# SkiMeter.net
KiCad netlist of a schematic drawn in EAGLE
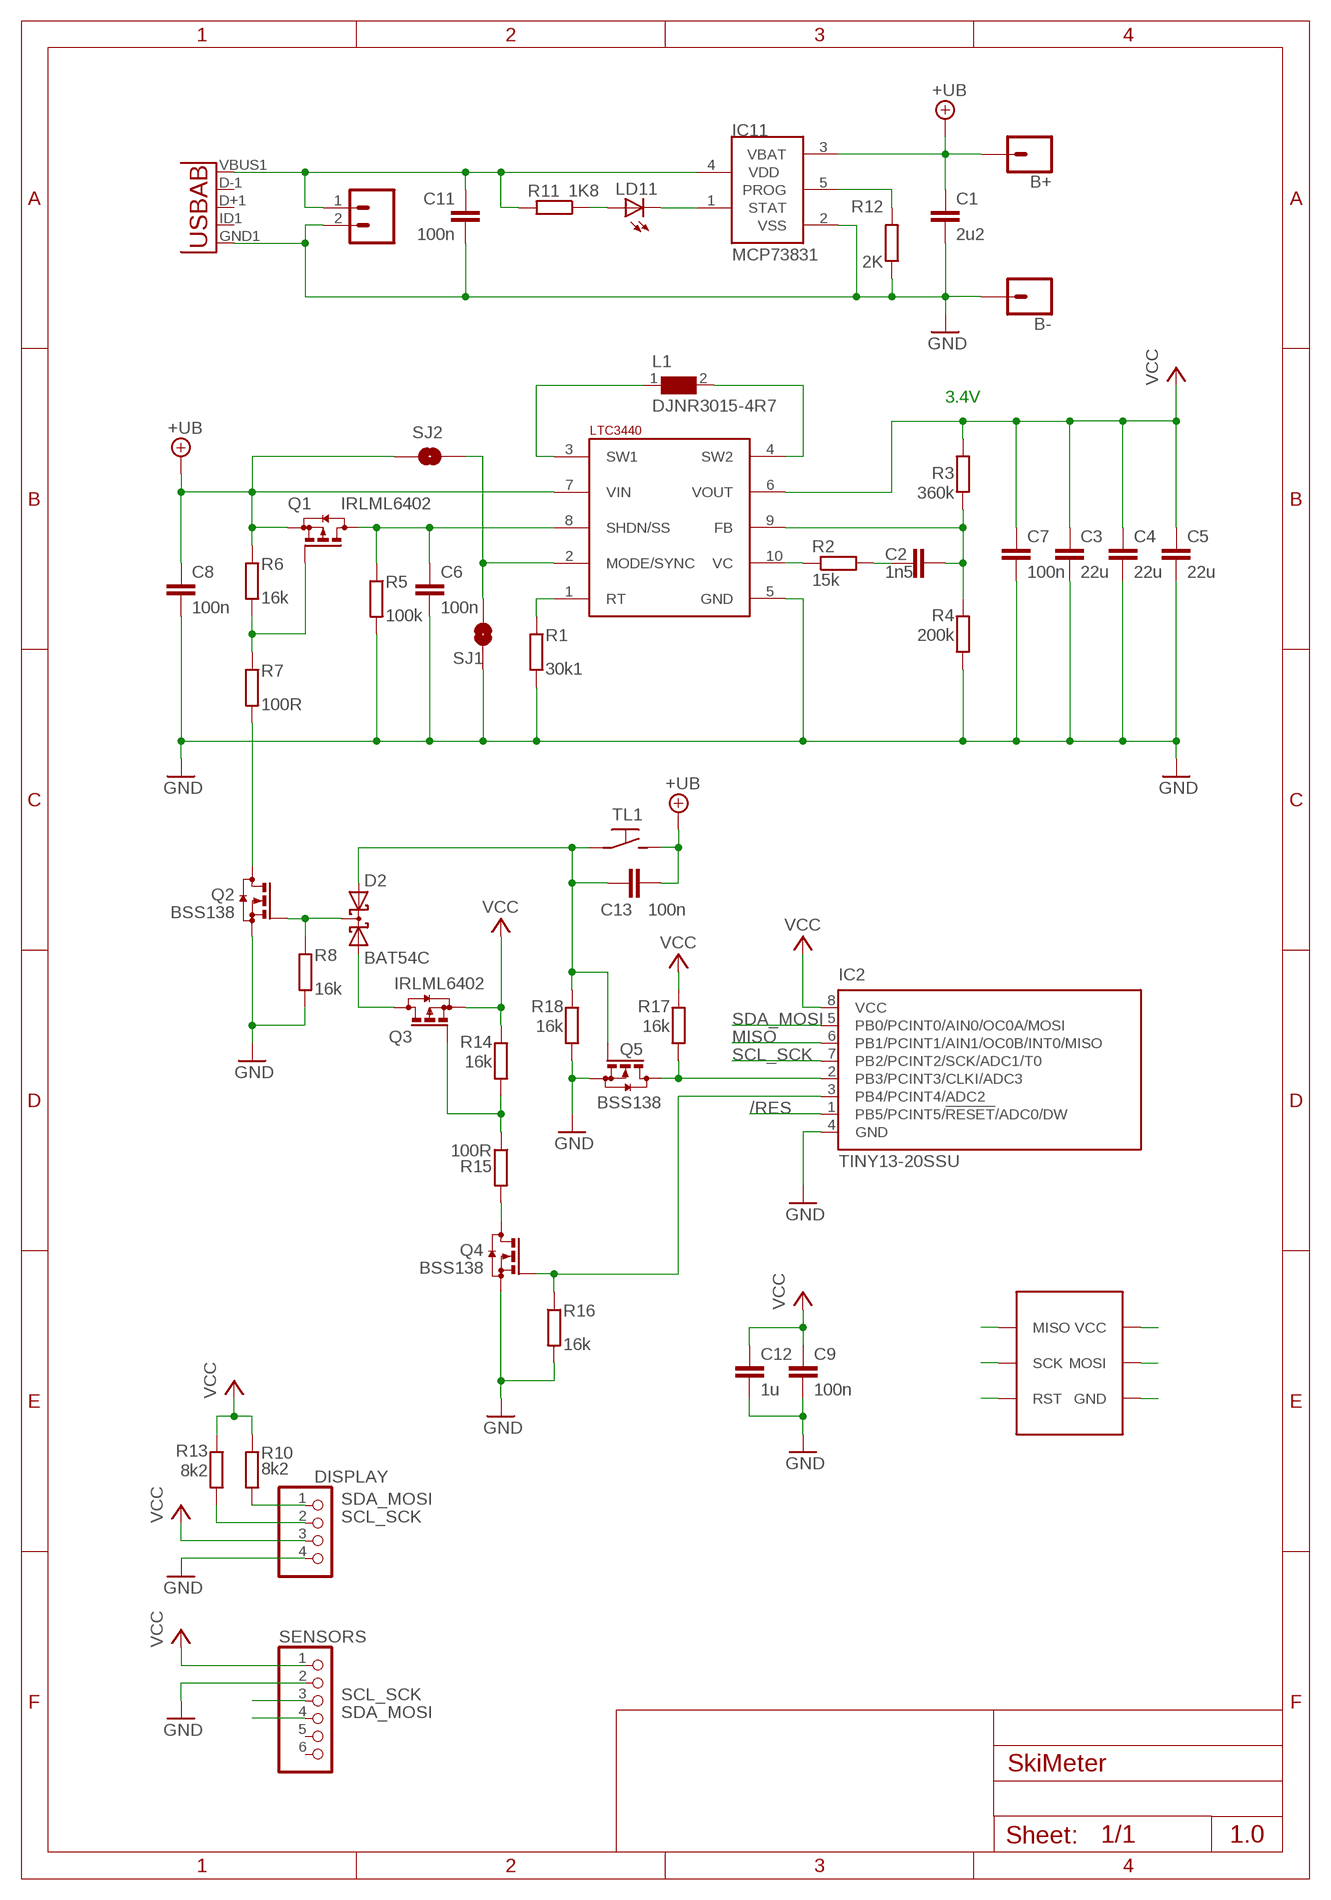
[diagram p0: schematic, sheet 1]

(export (version "E")
  (design (tool "Eeschema 10.0.6"))
  (components
    (comp (ref "+")
      (value "CONN_02")
      (footprint "eagle-import:1X02")
      (libsource (lib "eagle-import") (part "CONN_02"))
    )
    (comp (ref "B+")
      (value "CONN_01")
      (footprint "eagle-import:1X01")
      (libsource (lib "eagle-import") (part "CONN_01"))
    )
    (comp (ref "B-")
      (value "CONN_01")
      (footprint "eagle-import:1X01")
      (libsource (lib "eagle-import") (part "CONN_01"))
    )
    (comp (ref "C1")
      (value "2u2")
      (footprint "eagle-import:C0805")
      (libsource (lib "eagle-import") (part "C-EUC0805"))
    )
    (comp (ref "C2")
      (value "1n5")
      (footprint "eagle-import:C0805")
      (libsource (lib "eagle-import") (part "C-EUC0805"))
    )
    (comp (ref "C3")
      (value "22u")
      (footprint "eagle-import:C0805")
      (libsource (lib "eagle-import") (part "C-EUC0805"))
    )
    (comp (ref "C4")
      (value "22u")
      (footprint "eagle-import:C0805")
      (libsource (lib "eagle-import") (part "C-EUC0805"))
    )
    (comp (ref "C5")
      (value "22u")
      (footprint "eagle-import:C0805")
      (libsource (lib "eagle-import") (part "C-EUC0805"))
    )
    (comp (ref "C6")
      (value "100n")
      (footprint "eagle-import:C0805")
      (libsource (lib "eagle-import") (part "C-EUC0805"))
    )
    (comp (ref "C7")
      (value "100n")
      (footprint "eagle-import:C0805")
      (libsource (lib "eagle-import") (part "C-EUC0805"))
    )
    (comp (ref "C8")
      (value "100n")
      (footprint "eagle-import:C0805")
      (libsource (lib "eagle-import") (part "C-EUC0805"))
    )
    (comp (ref "C9")
      (value "100n")
      (footprint "eagle-import:C0805")
      (libsource (lib "eagle-import") (part "C-EUC0805"))
    )
    (comp (ref "C11")
      (value "100n")
      (footprint "eagle-import:C0805")
      (libsource (lib "eagle-import") (part "C-EUC0805"))
    )
    (comp (ref "C12")
      (value "1u")
      (footprint "eagle-import:C0805")
      (libsource (lib "eagle-import") (part "C-EUC0805"))
    )
    (comp (ref "C13")
      (value "100n")
      (footprint "eagle-import:C0805")
      (libsource (lib "eagle-import") (part "C-EUC0805"))
    )
    (comp (ref "D2")
      (value "BAT54C")
      (footprint "eagle-import:SOT23")
      (libsource (lib "eagle-import") (part "BAT54C"))
    )
    (comp (ref "DISPLAY")
      (value "PINHD-1X4")
      (footprint "eagle-import:1X04")
      (libsource (lib "eagle-import") (part "PINHD-1X4"))
    )
    (comp (ref "IC1")
      (value "LTC3440")
      (footprint "eagle-import:MSOP10")
      (libsource (lib "eagle-import") (part "LTC3440"))
    )
    (comp (ref "IC2")
      (value "TINY13-20SSU")
      (footprint "eagle-import:8S1")
      (fields (field (name "MPN") "ATTINY13-20SSU"))
      (libsource (lib "eagle-import") (part "TINY13SSU-20"))
    )
    (comp (ref "IC11")
      (value "MCP73831")
      (footprint "eagle-import:SOT23-5L")
      (libsource (lib "eagle-import") (part "MCP73831"))
    )
    (comp (ref "L1")
      (value "DJNR3015-4R7")
      (footprint "eagle-import:WE-LQS_3015")
      (libsource (lib "eagle-import") (part "WE-LQS_3015"))
    )
    (comp (ref "LD11")
      (value "LEDCHIPLED_0805")
      (footprint "eagle-import:CHIPLED_0805")
      (libsource (lib "eagle-import") (part "LEDCHIPLED_0805"))
    )
    (comp (ref "Q1")
      (value "IRLML6402")
      (footprint "eagle-import:SOT23")
      (libsource (lib "eagle-import") (part "BSS84"))
    )
    (comp (ref "Q2")
      (value "BSS138")
      (footprint "eagle-import:SOT23")
      (libsource (lib "eagle-import") (part "BSS123"))
    )
    (comp (ref "Q3")
      (value "IRLML6402")
      (footprint "eagle-import:SOT23")
      (libsource (lib "eagle-import") (part "BSS84"))
    )
    (comp (ref "Q4")
      (value "BSS138")
      (footprint "eagle-import:SOT23")
      (libsource (lib "eagle-import") (part "BSS123"))
    )
    (comp (ref "Q5")
      (value "BSS138")
      (footprint "eagle-import:SOT23")
      (libsource (lib "eagle-import") (part "BSS123"))
    )
    (comp (ref "R1")
      (value "30k1")
      (footprint "eagle-import:M0805")
      (libsource (lib "eagle-import") (part "R-EU_M0805"))
    )
    (comp (ref "R2")
      (value "15k")
      (footprint "eagle-import:M0805")
      (libsource (lib "eagle-import") (part "R-EU_M0805"))
    )
    (comp (ref "R3")
      (value "360k")
      (footprint "eagle-import:M0805")
      (libsource (lib "eagle-import") (part "R-EU_M0805"))
    )
    (comp (ref "R4")
      (value "200k")
      (footprint "eagle-import:M0805")
      (libsource (lib "eagle-import") (part "R-EU_M0805"))
    )
    (comp (ref "R5")
      (value "100k")
      (footprint "eagle-import:M0805")
      (libsource (lib "eagle-import") (part "R-EU_M0805"))
    )
    (comp (ref "R6")
      (value "16k")
      (footprint "eagle-import:M0805")
      (libsource (lib "eagle-import") (part "R-EU_M0805"))
    )
    (comp (ref "R7")
      (value "100R")
      (footprint "eagle-import:M0805")
      (libsource (lib "eagle-import") (part "R-EU_M0805"))
    )
    (comp (ref "R8")
      (value "16k")
      (footprint "eagle-import:M0805")
      (libsource (lib "eagle-import") (part "R-EU_M0805"))
    )
    (comp (ref "R10")
      (value "8k2")
      (footprint "eagle-import:M0805")
      (libsource (lib "eagle-import") (part "R-EU_M0805"))
    )
    (comp (ref "R11")
      (value "1K8")
      (footprint "eagle-import:M0805")
      (libsource (lib "eagle-import") (part "R-EU_M0805"))
    )
    (comp (ref "R12")
      (value "2K")
      (footprint "eagle-import:M0805")
      (libsource (lib "eagle-import") (part "R-EU_M0805"))
    )
    (comp (ref "R13")
      (value "8k2")
      (footprint "eagle-import:M0805")
      (libsource (lib "eagle-import") (part "R-EU_M0805"))
    )
    (comp (ref "R14")
      (value "16k")
      (footprint "eagle-import:M0805")
      (libsource (lib "eagle-import") (part "R-EU_M0805"))
    )
    (comp (ref "R15")
      (value "100R")
      (footprint "eagle-import:M0805")
      (libsource (lib "eagle-import") (part "R-EU_M0805"))
    )
    (comp (ref "R16")
      (value "16k")
      (footprint "eagle-import:M0805")
      (libsource (lib "eagle-import") (part "R-EU_M0805"))
    )
    (comp (ref "R17")
      (value "16k")
      (footprint "eagle-import:M0805")
      (libsource (lib "eagle-import") (part "R-EU_M0805"))
    )
    (comp (ref "R18")
      (value "16k")
      (footprint "eagle-import:M0805")
      (libsource (lib "eagle-import") (part "R-EU_M0805"))
    )
    (comp (ref "SENSORS")
      (value "PINHD-1X6")
      (footprint "eagle-import:1X06")
      (libsource (lib "eagle-import") (part "PINHD-1X6"))
    )
    (comp (ref "SJ1")
      (value "SOLDERJUMPERNO")
      (footprint "eagle-import:SJ_2S-NO")
      (libsource (lib "eagle-import") (part "SOLDERJUMPERNO"))
    )
    (comp (ref "SJ2")
      (value "SOLDERJUMPERTRACE")
      (footprint "eagle-import:SJ_2S-TRACE")
      (libsource (lib "eagle-import") (part "SOLDERJUMPERTRACE"))
    )
    (comp (ref "TL1")
      (value "TS1107GS")
      (footprint "eagle-import:TS1107GS")
      (libsource (lib "eagle-import") (part "TS1107GS"))
    )
    (comp (ref "U$1")
      (value "ISP")
      (footprint "eagle-import:ISP_PCB")
      (libsource (lib "eagle-import") (part "ISP"))
    )
    (comp (ref "U1")
      (value "USB\"\"")
      (footprint "eagle-import:USB-MICRO-SMD")
      (libsource (lib "eagle-import") (part "USB{dblquote}{dblquote}"))
    )
  )
  (nets
    (net (code "1") (name "+UB") (class "Default")
      (node (ref "B+") (pin "1") (pinfunction "1_1") (pintype "passive"))
      (node (ref "C1") (pin "1") (pinfunction "1_1") (pintype "passive"))
      (node (ref "C13") (pin "1") (pinfunction "1_1") (pintype "passive"))
      (node (ref "C8") (pin "1") (pinfunction "1_1") (pintype "passive"))
      (node (ref "IC1") (pin "7") (pinfunction "VIN_7") (pintype "bidirectional"))
      (node (ref "IC11") (pin "3") (pinfunction "VBAT_3") (pintype "bidirectional"))
      (node (ref "Q1") (pin "2") (pinfunction "S_2") (pintype "passive"))
      (node (ref "R6") (pin "1") (pinfunction "1_1") (pintype "passive"))
      (node (ref "SJ2") (pin "2") (pinfunction "2_2") (pintype "passive"))
      (node (ref "TL1") (pin "P$2") (pinfunction "S_P$2") (pintype "passive"))
    )
    (net (code "2") (name "/MISO") (class "Default")
      (node (ref "IC2") (pin "6") (pinfunction "PB1/PCINT1/AIN1/OC0B/INT0/MISO_6") (pintype "bidirectional"))
      (node (ref "U$1") (pin "P$1") (pinfunction "MISO_P$1") (pintype "bidirectional"))
    )
    (net (code "3") (name "/SCL_SCK") (class "Default")
      (node (ref "DISPLAY") (pin "2") (pinfunction "2_2") (pintype "passive"))
      (node (ref "IC2") (pin "7") (pinfunction "PB2/PCINT2/SCK/ADC1/T0_7") (pintype "bidirectional"))
      (node (ref "R13") (pin "2") (pinfunction "2_2") (pintype "passive"))
      (node (ref "SENSORS") (pin "3") (pinfunction "3_3") (pintype "passive"))
      (node (ref "U$1") (pin "P$3") (pinfunction "SCK_P$3") (pintype "bidirectional"))
    )
    (net (code "4") (name "/SDA_MOSI") (class "Default")
      (node (ref "DISPLAY") (pin "1") (pinfunction "1_1") (pintype "passive"))
      (node (ref "IC2") (pin "5") (pinfunction "PB0/PCINT0/AIN0/OC0A/MOSI_5") (pintype "bidirectional"))
      (node (ref "R10") (pin "2") (pinfunction "2_2") (pintype "passive"))
      (node (ref "SENSORS") (pin "4") (pinfunction "4_4") (pintype "passive"))
      (node (ref "U$1") (pin "P$4") (pinfunction "MOSI_P$4") (pintype "bidirectional"))
    )
    (net (code "5") (name "/{slash}RES") (class "Default")
      (node (ref "IC2") (pin "1") (pinfunction "PB5/PCINT5/~{RESET}/ADC0/DW_1") (pintype "bidirectional"))
      (node (ref "U$1") (pin "P$5") (pinfunction "RST_P$5") (pintype "bidirectional"))
    )
    (net (code "6") (name "GND") (class "Default")
      (node (ref "+") (pin "2") (pinfunction "2_2") (pintype "passive"))
      (node (ref "B-") (pin "1") (pinfunction "1_1") (pintype "passive"))
      (node (ref "C1") (pin "2") (pinfunction "2_2") (pintype "passive"))
      (node (ref "C11") (pin "1") (pinfunction "1_1") (pintype "passive"))
      (node (ref "C12") (pin "2") (pinfunction "2_2") (pintype "passive"))
      (node (ref "C3") (pin "2") (pinfunction "2_2") (pintype "passive"))
      (node (ref "C4") (pin "2") (pinfunction "2_2") (pintype "passive"))
      (node (ref "C5") (pin "2") (pinfunction "2_2") (pintype "passive"))
      (node (ref "C6") (pin "2") (pinfunction "2_2") (pintype "passive"))
      (node (ref "C7") (pin "2") (pinfunction "2_2") (pintype "passive"))
      (node (ref "C8") (pin "2") (pinfunction "2_2") (pintype "passive"))
      (node (ref "C9") (pin "2") (pinfunction "2_2") (pintype "passive"))
      (node (ref "DISPLAY") (pin "4") (pinfunction "4_4") (pintype "passive"))
      (node (ref "IC1") (pin "5") (pinfunction "GND_5") (pintype "bidirectional"))
      (node (ref "IC11") (pin "2") (pinfunction "VSS_2") (pintype "bidirectional"))
      (node (ref "IC2") (pin "4") (pinfunction "GND_4") (pintype "power_in"))
      (node (ref "Q2") (pin "2") (pinfunction "S_2") (pintype "passive"))
      (node (ref "Q4") (pin "2") (pinfunction "S_2") (pintype "passive"))
      (node (ref "Q5") (pin "2") (pinfunction "S_2") (pintype "passive"))
      (node (ref "R1") (pin "2") (pinfunction "2_2") (pintype "passive"))
      (node (ref "R12") (pin "1") (pinfunction "1_1") (pintype "passive"))
      (node (ref "R16") (pin "2") (pinfunction "2_2") (pintype "passive"))
      (node (ref "R18") (pin "2") (pinfunction "2_2") (pintype "passive"))
      (node (ref "R4") (pin "1") (pinfunction "1_1") (pintype "passive"))
      (node (ref "R5") (pin "2") (pinfunction "2_2") (pintype "passive"))
      (node (ref "R8") (pin "2") (pinfunction "2_2") (pintype "passive"))
      (node (ref "SENSORS") (pin "2") (pinfunction "2_2") (pintype "passive"))
      (node (ref "SJ1") (pin "1") (pinfunction "1_1") (pintype "passive"))
      (node (ref "U$1") (pin "P$6") (pinfunction "GND_P$6") (pintype "bidirectional"))
      (node (ref "U1") (pin "GND1") (pinfunction "GND_GND1") (pintype "bidirectional"))
    )
    (net (code "7") (name "Net-(C2-Pad1)") (class "Default")
      (node (ref "C2") (pin "1") (pinfunction "1_1") (pintype "passive"))
      (node (ref "R2") (pin "2") (pinfunction "2_2") (pintype "passive"))
    )
    (net (code "8") (name "Net-(D2-A1)") (class "Default")
      (node (ref "D2") (pin "1") (pinfunction "A1_1") (pintype "passive"))
      (node (ref "Q3") (pin "3") (pinfunction "D_3") (pintype "passive"))
    )
    (net (code "9") (name "Net-(D2-A2)") (class "Default")
      (node (ref "C13") (pin "2") (pinfunction "2_2") (pintype "passive"))
      (node (ref "D2") (pin "2") (pinfunction "A2_2") (pintype "passive"))
      (node (ref "Q5") (pin "1") (pinfunction "G_1") (pintype "passive"))
      (node (ref "R18") (pin "1") (pinfunction "1_1") (pintype "passive"))
      (node (ref "TL1") (pin "P$1") (pinfunction "P_P$1") (pintype "passive"))
    )
    (net (code "10") (name "Net-(D2-CC)") (class "Default")
      (node (ref "D2") (pin "3") (pinfunction "CC_3") (pintype "passive"))
      (node (ref "Q2") (pin "1") (pinfunction "G_1") (pintype "passive"))
      (node (ref "R8") (pin "1") (pinfunction "1_1") (pintype "passive"))
    )
    (net (code "11") (name "Net-(IC1-FB)") (class "Default")
      (node (ref "C2") (pin "2") (pinfunction "2_2") (pintype "passive"))
      (node (ref "IC1") (pin "9") (pinfunction "FB_9") (pintype "bidirectional"))
      (node (ref "R3") (pin "1") (pinfunction "1_1") (pintype "passive"))
      (node (ref "R4") (pin "2") (pinfunction "2_2") (pintype "passive"))
    )
    (net (code "12") (name "Net-(IC1-MODE{slash}SYNC)") (class "Default")
      (node (ref "IC1") (pin "2") (pinfunction "MODE/SYNC_2") (pintype "bidirectional"))
      (node (ref "SJ1") (pin "2") (pinfunction "2_2") (pintype "passive"))
      (node (ref "SJ2") (pin "1") (pinfunction "1_1") (pintype "passive"))
    )
    (net (code "13") (name "Net-(IC1-RT)") (class "Default")
      (node (ref "IC1") (pin "1") (pinfunction "RT_1") (pintype "bidirectional"))
      (node (ref "R1") (pin "1") (pinfunction "1_1") (pintype "passive"))
    )
    (net (code "14") (name "Net-(IC1-SHDN{slash}SS)") (class "Default")
      (node (ref "C6") (pin "1") (pinfunction "1_1") (pintype "passive"))
      (node (ref "IC1") (pin "8") (pinfunction "SHDN/SS_8") (pintype "bidirectional"))
      (node (ref "Q1") (pin "3") (pinfunction "D_3") (pintype "passive"))
      (node (ref "R5") (pin "1") (pinfunction "1_1") (pintype "passive"))
    )
    (net (code "15") (name "Net-(IC1-SW1)") (class "Default")
      (node (ref "IC1") (pin "3") (pinfunction "SW1_3") (pintype "bidirectional"))
      (node (ref "L1") (pin "1") (pinfunction "1_1") (pintype "passive"))
    )
    (net (code "16") (name "Net-(IC1-SW2)") (class "Default")
      (node (ref "IC1") (pin "4") (pinfunction "SW2_4") (pintype "bidirectional"))
      (node (ref "L1") (pin "2") (pinfunction "2_2") (pintype "passive"))
    )
    (net (code "17") (name "Net-(IC1-VC)") (class "Default")
      (node (ref "IC1") (pin "10") (pinfunction "VC_10") (pintype "bidirectional"))
      (node (ref "R2") (pin "1") (pinfunction "1_1") (pintype "passive"))
    )
    (net (code "18") (name "Net-(IC2-PB3{slash}PCINT3{slash}CLKI{slash}ADC3)") (class "Default")
      (node (ref "IC2") (pin "2") (pinfunction "PB3/PCINT3/CLKI/ADC3_2") (pintype "bidirectional"))
      (node (ref "Q5") (pin "3") (pinfunction "D_3") (pintype "passive"))
      (node (ref "R17") (pin "2") (pinfunction "2_2") (pintype "passive"))
    )
    (net (code "19") (name "Net-(IC2-PB4{slash}PCINT4{slash}ADC2)") (class "Default")
      (node (ref "IC2") (pin "3") (pinfunction "PB4/PCINT4/ADC2_3") (pintype "bidirectional"))
      (node (ref "Q4") (pin "1") (pinfunction "G_1") (pintype "passive"))
      (node (ref "R16") (pin "1") (pinfunction "1_1") (pintype "passive"))
    )
    (net (code "20") (name "Net-(IC11-PROG)") (class "Default")
      (node (ref "IC11") (pin "5") (pinfunction "PROG_5") (pintype "bidirectional"))
      (node (ref "R12") (pin "2") (pinfunction "2_2") (pintype "passive"))
    )
    (net (code "21") (name "Net-(IC11-STAT)") (class "Default")
      (node (ref "IC11") (pin "1") (pinfunction "STAT_1") (pintype "bidirectional"))
      (node (ref "LD11") (pin "C") (pinfunction "C_C") (pintype "passive"))
    )
    (net (code "22") (name "Net-(IC11-VDD)") (class "Default")
      (node (ref "+") (pin "1") (pinfunction "1_1") (pintype "passive"))
      (node (ref "C11") (pin "2") (pinfunction "2_2") (pintype "passive"))
      (node (ref "IC11") (pin "4") (pinfunction "VDD_4") (pintype "bidirectional"))
      (node (ref "R11") (pin "2") (pinfunction "2_2") (pintype "passive"))
      (node (ref "U1") (pin "VBUS1") (pinfunction "VBUS_VBUS1") (pintype "bidirectional"))
    )
    (net (code "23") (name "Net-(LD11-PadA)") (class "Default")
      (node (ref "LD11") (pin "A") (pinfunction "A_A") (pintype "passive"))
      (node (ref "R11") (pin "1") (pinfunction "1_1") (pintype "passive"))
    )
    (net (code "24") (name "Net-(Q1-G)") (class "Default")
      (node (ref "Q1") (pin "1") (pinfunction "G_1") (pintype "passive"))
      (node (ref "R6") (pin "2") (pinfunction "2_2") (pintype "passive"))
      (node (ref "R7") (pin "1") (pinfunction "1_1") (pintype "passive"))
    )
    (net (code "25") (name "Net-(Q2-D)") (class "Default")
      (node (ref "Q2") (pin "3") (pinfunction "D_3") (pintype "passive"))
      (node (ref "R7") (pin "2") (pinfunction "2_2") (pintype "passive"))
    )
    (net (code "26") (name "Net-(Q3-G)") (class "Default")
      (node (ref "Q3") (pin "1") (pinfunction "G_1") (pintype "passive"))
      (node (ref "R14") (pin "2") (pinfunction "2_2") (pintype "passive"))
      (node (ref "R15") (pin "1") (pinfunction "1_1") (pintype "passive"))
    )
    (net (code "27") (name "Net-(Q4-D)") (class "Default")
      (node (ref "Q4") (pin "3") (pinfunction "D_3") (pintype "passive"))
      (node (ref "R15") (pin "2") (pinfunction "2_2") (pintype "passive"))
    )
    (net (code "28") (name "VCC") (class "Default")
      (node (ref "C12") (pin "1") (pinfunction "1_1") (pintype "passive"))
      (node (ref "C3") (pin "1") (pinfunction "1_1") (pintype "passive"))
      (node (ref "C4") (pin "1") (pinfunction "1_1") (pintype "passive"))
      (node (ref "C5") (pin "1") (pinfunction "1_1") (pintype "passive"))
      (node (ref "C7") (pin "1") (pinfunction "1_1") (pintype "passive"))
      (node (ref "C9") (pin "1") (pinfunction "1_1") (pintype "passive"))
      (node (ref "DISPLAY") (pin "3") (pinfunction "3_3") (pintype "passive"))
      (node (ref "IC1") (pin "6") (pinfunction "VOUT_6") (pintype "bidirectional"))
      (node (ref "IC2") (pin "8") (pinfunction "VCC_8") (pintype "power_in"))
      (node (ref "Q3") (pin "2") (pinfunction "S_2") (pintype "passive"))
      (node (ref "R10") (pin "1") (pinfunction "1_1") (pintype "passive"))
      (node (ref "R13") (pin "1") (pinfunction "1_1") (pintype "passive"))
      (node (ref "R14") (pin "1") (pinfunction "1_1") (pintype "passive"))
      (node (ref "R17") (pin "1") (pinfunction "1_1") (pintype "passive"))
      (node (ref "R3") (pin "2") (pinfunction "2_2") (pintype "passive"))
      (node (ref "SENSORS") (pin "1") (pinfunction "1_1") (pintype "passive"))
      (node (ref "U$1") (pin "P$2") (pinfunction "VCC_P$2") (pintype "bidirectional"))
    )
    (net (code "29") (name "unconnected-(SENSORS-Pad5)") (class "Default")
      (node (ref "SENSORS") (pin "5") (pinfunction "5_5") (pintype "passive"))
    )
    (net (code "30") (name "unconnected-(SENSORS-Pad6)") (class "Default")
      (node (ref "SENSORS") (pin "6") (pinfunction "6_6") (pintype "passive"))
    )
    (net (code "31") (name "unconnected-(U1-D+-PadD+1)") (class "Default")
      (node (ref "U1") (pin "D+1") (pinfunction "D+_D+1") (pintype "bidirectional"))
    )
    (net (code "32") (name "unconnected-(U1-D--PadD-1)") (class "Default")
      (node (ref "U1") (pin "D-1") (pinfunction "D-_D-1") (pintype "bidirectional"))
    )
    (net (code "33") (name "unconnected-(U1-USBID-PadID1)") (class "Default")
      (node (ref "U1") (pin "ID1") (pinfunction "USBID_ID1") (pintype "bidirectional"))
    )
  )
)
